# picoAva-Rev3-Boost.net
KiCad netlist of a schematic drawn in EAGLE
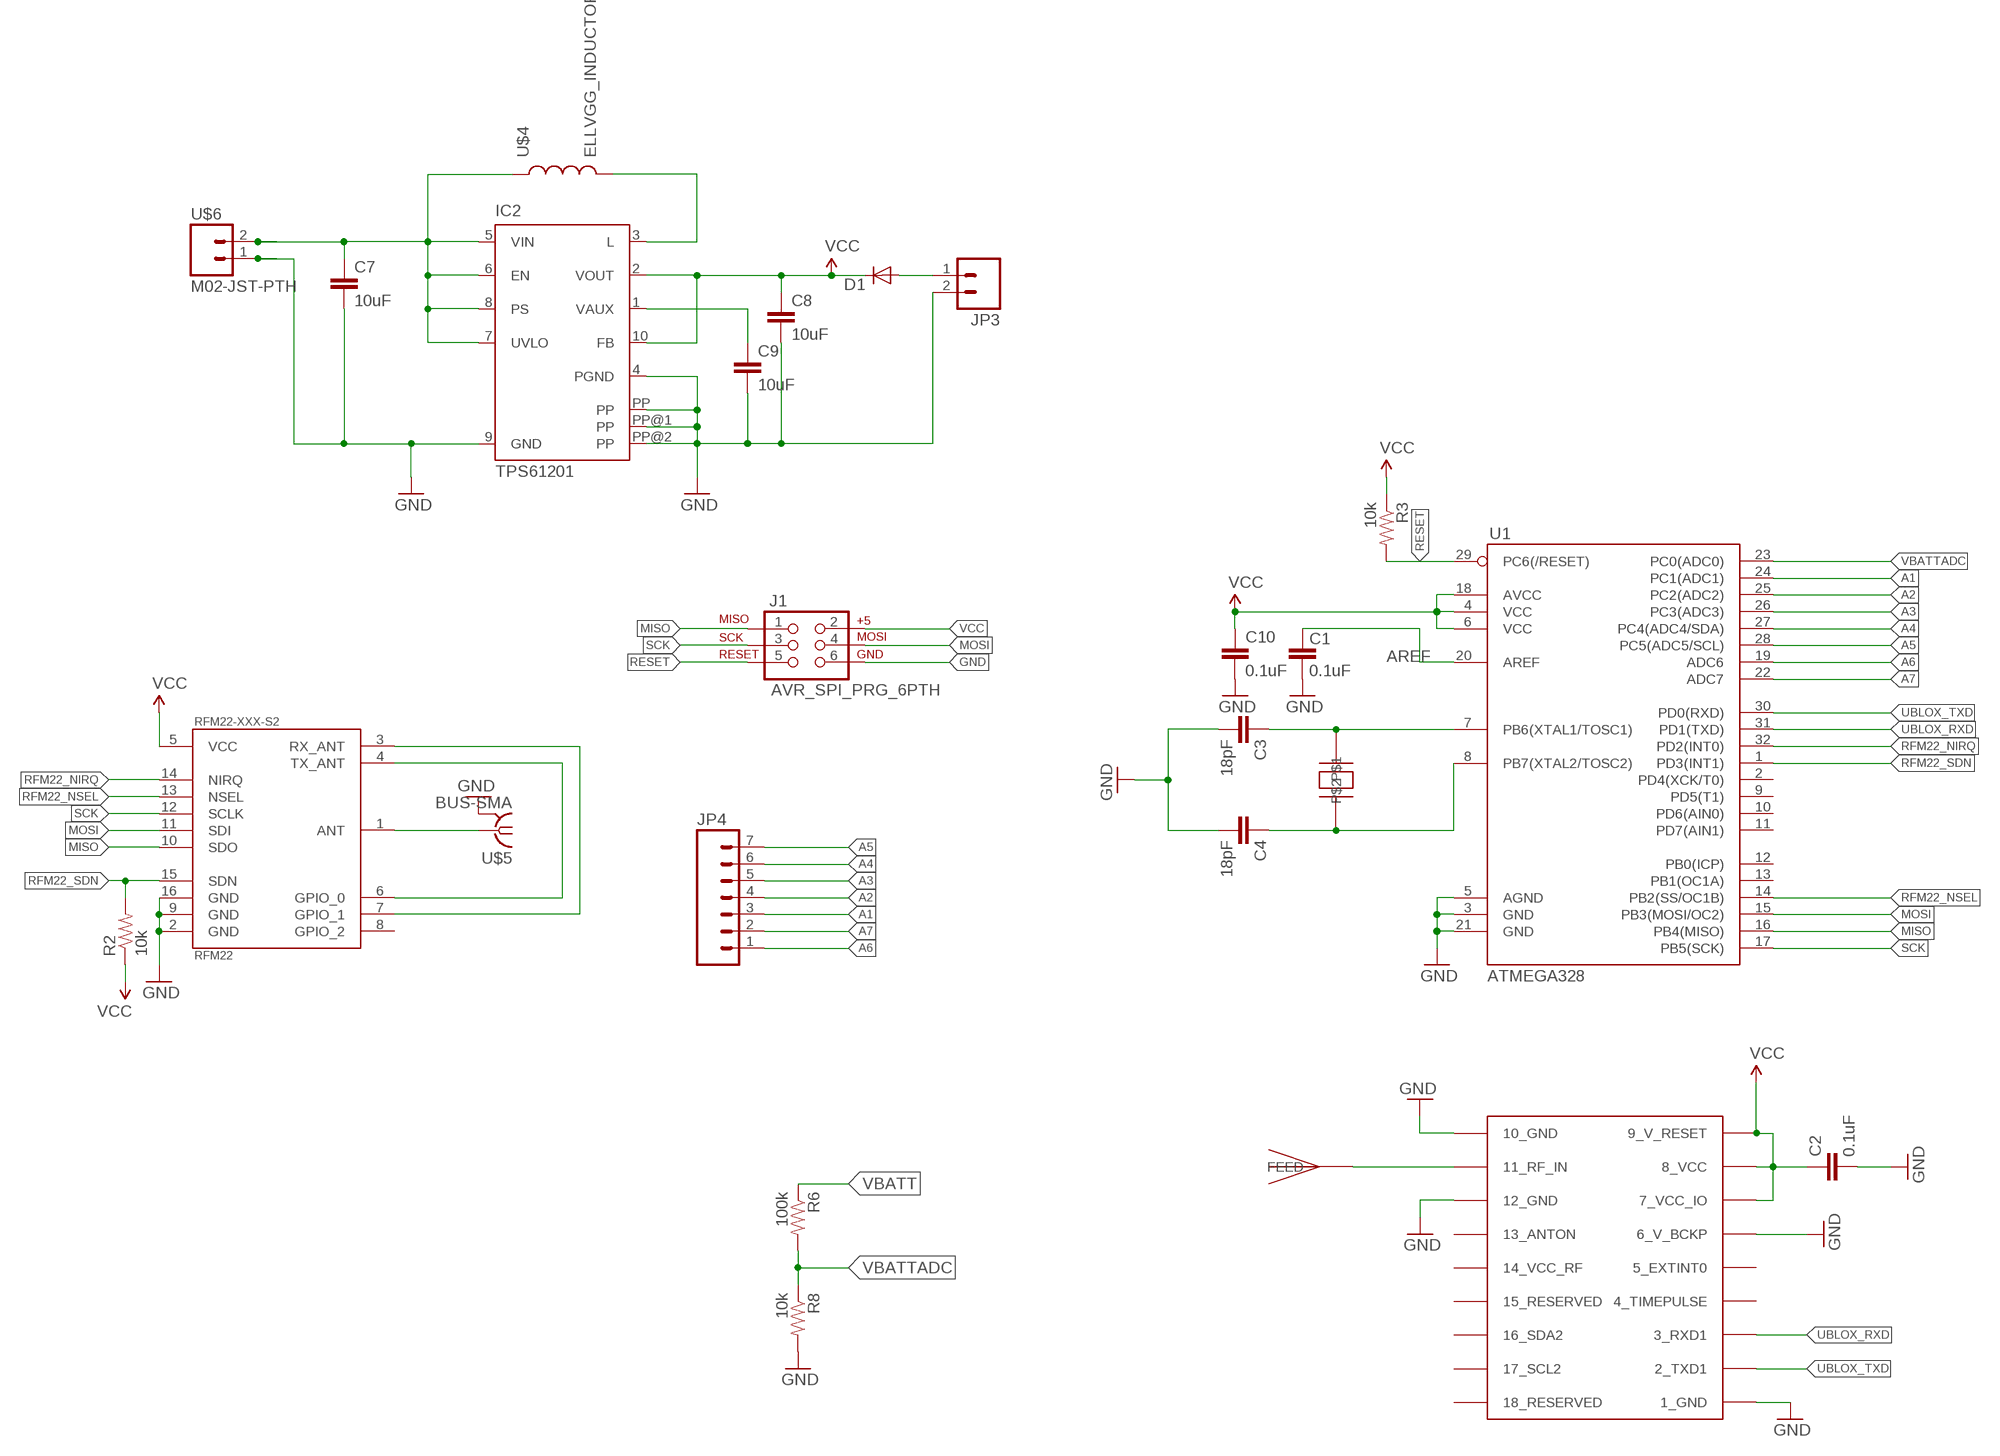
[diagram p0: schematic, sheet 1]

(export (version "E")
  (design (tool "Eeschema 10.0.6"))
  (components
    (comp (ref "C1")
      (value "0.1uF")
      (footprint "eagle-import:0402-CAP")
      (libsource (lib "eagle-import") (part "CAP0402-CAP"))
    )
    (comp (ref "C2")
      (value "0.1uF")
      (footprint "eagle-import:0402-CAP")
      (libsource (lib "eagle-import") (part "CAP0402-CAP"))
    )
    (comp (ref "C3")
      (value "18pF")
      (footprint "eagle-import:0402-CAP")
      (libsource (lib "eagle-import") (part "CAP0402-CAP"))
    )
    (comp (ref "C4")
      (value "18pF")
      (footprint "eagle-import:0402-CAP")
      (libsource (lib "eagle-import") (part "CAP0402-CAP"))
    )
    (comp (ref "C7")
      (value "10uF")
      (footprint "eagle-import:1206")
      (libsource (lib "eagle-import") (part "CAP1206"))
    )
    (comp (ref "C8")
      (value "10uF")
      (footprint "eagle-import:1206")
      (libsource (lib "eagle-import") (part "CAP1206"))
    )
    (comp (ref "C9")
      (value "10uF")
      (footprint "eagle-import:1206")
      (libsource (lib "eagle-import") (part "CAP1206"))
    )
    (comp (ref "C10")
      (value "0.1uF")
      (footprint "eagle-import:0402-CAP")
      (libsource (lib "eagle-import") (part "CAP0402-CAP"))
    )
    (comp (ref "D1")
      (value "DIODESMA")
      (footprint "eagle-import:SMA-DIODE")
      (libsource (lib "eagle-import") (part "DIODESMA"))
    )
    (comp (ref "IC2")
      (value "TPS61201")
      (footprint "eagle-import:S-PDSO-N10")
      (fields (field (name "MPN") "TPS61201DRCT"))
      (libsource (lib "eagle-import") (part "TPS61201"))
    )
    (comp (ref "J1")
      (value "AVR_SPI_PRG_6PTH")
      (footprint "eagle-import:2X3")
      (libsource (lib "eagle-import") (part "AVR_SPI_PRG_6PTH"))
    )
    (comp (ref "JP3")
      (value "M02PTH")
      (footprint "eagle-import:1X02")
      (libsource (lib "eagle-import") (part "M02PTH"))
    )
    (comp (ref "JP4")
      (value "M07")
      (footprint "eagle-import:1X07")
      (libsource (lib "eagle-import") (part "M07"))
    )
    (comp (ref "R2")
      (value "10k")
      (footprint "eagle-import:0402-RES")
      (libsource (lib "eagle-import") (part "RESISTOR0402-RES"))
    )
    (comp (ref "R3")
      (value "10k")
      (footprint "eagle-import:0402-RES")
      (libsource (lib "eagle-import") (part "RESISTOR0402-RES"))
    )
    (comp (ref "R6")
      (value "100k")
      (footprint "eagle-import:0402-RES")
      (libsource (lib "eagle-import") (part "RESISTOR0402-RES"))
    )
    (comp (ref "R8")
      (value "10k")
      (footprint "eagle-import:0402-RES")
      (libsource (lib "eagle-import") (part "RESISTOR0402-RES"))
    )
    (comp (ref "RFM22-XXX-S2")
      (value "RFM22")
      (footprint "eagle-import:RFM22-XXX-S2")
      (libsource (lib "eagle-import") (part "RFM22"))
    )
    (comp (ref "U$1")
      (value "UBLOX_MAX-6")
      (footprint "eagle-import:UBLOX_MAX-6")
      (libsource (lib "eagle-import") (part "UBLOX_MAX-6"))
    )
    (comp (ref "U$2")
      (value "ABRACON_ABM3_CRYSTAL")
      (footprint "eagle-import:ABRACON_ABM3_CRYSTAL")
      (libsource (lib "eagle-import") (part "ABRACON_ABM3_CRYSTAL"))
    )
    (comp (ref "U$3")
      (value "JTI_ANTENNA-1575AT43A40")
      (footprint "eagle-import:JTI_ANTENNA-1575AT43A40")
      (libsource (lib "eagle-import") (part "JTI_ANTENNA-1575AT43A40"))
    )
    (comp (ref "U$4")
      (value "ELLVGG_INDUCTOR")
      (footprint "eagle-import:ELLVGG_INDUCTOR")
      (libsource (lib "eagle-import") (part "ELLVGG_INDUCTOR"))
    )
    (comp (ref "U$5")
      (value "BUS-SMA")
      (footprint "eagle-import:BUS-SMA")
      (libsource (lib "eagle-import") (part "BUS-SMA"))
    )
    (comp (ref "U$6")
      (value "M02-JST-PTH")
      (footprint "eagle-import:M02-JST-PTH")
      (libsource (lib "eagle-import") (part "M02-JST-PTH"))
    )
    (comp (ref "U1")
      (value "ATMEGA328")
      (footprint "eagle-import:TQFP32-08")
      (libsource (lib "eagle-import") (part "ATMEGA168"))
    )
  )
  (nets
    (net (code "1") (name "/AREF") (class "Default")
      (node (ref "C1") (pin "2") (pinfunction "2_2") (pintype "passive"))
      (node (ref "U1") (pin "20") (pinfunction "AREF_20") (pintype "bidirectional"))
    )
    (net (code "2") (name "A1") (class "Default")
      (node (ref "JP4") (pin "3") (pinfunction "3_3") (pintype "passive"))
      (node (ref "U1") (pin "24") (pinfunction "PC1(ADC1)_24") (pintype "bidirectional"))
    )
    (net (code "3") (name "A2") (class "Default")
      (node (ref "JP4") (pin "4") (pinfunction "4_4") (pintype "passive"))
      (node (ref "U1") (pin "25") (pinfunction "PC2(ADC2)_25") (pintype "bidirectional"))
    )
    (net (code "4") (name "A3") (class "Default")
      (node (ref "JP4") (pin "5") (pinfunction "5_5") (pintype "passive"))
      (node (ref "U1") (pin "26") (pinfunction "PC3(ADC3)_26") (pintype "bidirectional"))
    )
    (net (code "5") (name "A4") (class "Default")
      (node (ref "JP4") (pin "6") (pinfunction "6_6") (pintype "passive"))
      (node (ref "U1") (pin "27") (pinfunction "PC4(ADC4/SDA)_27") (pintype "bidirectional"))
    )
    (net (code "6") (name "A5") (class "Default")
      (node (ref "JP4") (pin "7") (pinfunction "7_7") (pintype "passive"))
      (node (ref "U1") (pin "28") (pinfunction "PC5(ADC5/SCL)_28") (pintype "bidirectional"))
    )
    (net (code "7") (name "A6") (class "Default")
      (node (ref "JP4") (pin "1") (pinfunction "1_1") (pintype "passive"))
      (node (ref "U1") (pin "19") (pinfunction "ADC6_19") (pintype "bidirectional"))
    )
    (net (code "8") (name "A7") (class "Default")
      (node (ref "JP4") (pin "2") (pinfunction "2_2") (pintype "passive"))
      (node (ref "U1") (pin "22") (pinfunction "ADC7_22") (pintype "bidirectional"))
    )
    (net (code "9") (name "GND") (class "Default")
      (node (ref "C1") (pin "1") (pinfunction "1_1") (pintype "passive"))
      (node (ref "C10") (pin "2") (pinfunction "2_2") (pintype "passive"))
      (node (ref "C2") (pin "2") (pinfunction "2_2") (pintype "passive"))
      (node (ref "C3") (pin "2") (pinfunction "2_2") (pintype "passive"))
      (node (ref "C4") (pin "2") (pinfunction "2_2") (pintype "passive"))
      (node (ref "C7") (pin "2") (pinfunction "2_2") (pintype "passive"))
      (node (ref "C8") (pin "2") (pinfunction "2_2") (pintype "passive"))
      (node (ref "C9") (pin "2") (pinfunction "2_2") (pintype "passive"))
      (node (ref "IC2") (pin "4") (pinfunction "PGND_4") (pintype "power_in"))
      (node (ref "IC2") (pin "9") (pinfunction "GND_9") (pintype "power_in"))
      (node (ref "IC2") (pin "PP") (pinfunction "PP_PP") (pintype "power_in"))
      (node (ref "IC2") (pin "PP@1") (pinfunction "PP_PP@1") (pintype "power_in"))
      (node (ref "IC2") (pin "PP@2") (pinfunction "PP_PP@2") (pintype "power_in"))
      (node (ref "J1") (pin "6") (pinfunction "6_6") (pintype "passive"))
      (node (ref "JP3") (pin "2") (pinfunction "2_2") (pintype "passive"))
      (node (ref "R8") (pin "2") (pinfunction "2_2") (pintype "passive"))
      (node (ref "RFM22-XXX-S2") (pin "16") (pinfunction "GND_16") (pintype "power_in"))
      (node (ref "RFM22-XXX-S2") (pin "2") (pinfunction "GND_2") (pintype "power_in"))
      (node (ref "RFM22-XXX-S2") (pin "9") (pinfunction "GND_9") (pintype "power_in"))
      (node (ref "U$1") (pin "10_GND") (pinfunction "10_GND_10_GND") (pintype "bidirectional"))
      (node (ref "U$1") (pin "12_GND") (pinfunction "12_GND_12_GND") (pintype "bidirectional"))
      (node (ref "U$1") (pin "1_GND") (pinfunction "1_GND_1_GND") (pintype "bidirectional"))
      (node (ref "U$1") (pin "6_V_BCKP") (pinfunction "6_V_BCKP_6_V_BCKP") (pintype "bidirectional"))
      (node (ref "U$5") (pin "2") (pinfunction "GND_2") (pintype "power_in"))
      (node (ref "U$5") (pin "3") (pinfunction "GND_3") (pintype "power_in"))
      (node (ref "U$5") (pin "4") (pinfunction "GND_4") (pintype "power_in"))
      (node (ref "U$5") (pin "5") (pinfunction "GND_5") (pintype "power_in"))
      (node (ref "U$6") (pin "1") (pinfunction "1_1") (pintype "passive"))
      (node (ref "U1") (pin "21") (pinfunction "GND_21") (pintype "bidirectional"))
      (node (ref "U1") (pin "3") (pinfunction "GND_3") (pintype "bidirectional"))
      (node (ref "U1") (pin "5") (pinfunction "AGND_5") (pintype "bidirectional"))
    )
    (net (code "10") (name "MISO") (class "Default")
      (node (ref "J1") (pin "1") (pinfunction "1_1") (pintype "passive"))
      (node (ref "RFM22-XXX-S2") (pin "10") (pinfunction "SDO_10") (pintype "output"))
      (node (ref "U1") (pin "16") (pinfunction "PB4(MISO)_16") (pintype "bidirectional"))
    )
    (net (code "11") (name "MOSI") (class "Default")
      (node (ref "J1") (pin "4") (pinfunction "4_4") (pintype "passive"))
      (node (ref "RFM22-XXX-S2") (pin "11") (pinfunction "SDI_11") (pintype "input"))
      (node (ref "U1") (pin "15") (pinfunction "PB3(MOSI/OC2)_15") (pintype "bidirectional"))
    )
    (net (code "12") (name "Net-(D1-PadA)") (class "Default")
      (node (ref "D1") (pin "A") (pinfunction "A_A") (pintype "passive"))
      (node (ref "JP3") (pin "1") (pinfunction "1_1") (pintype "passive"))
    )
    (net (code "13") (name "Net-(IC2-L)") (class "Default")
      (node (ref "IC2") (pin "3") (pinfunction "L_3") (pintype "input"))
      (node (ref "U$4") (pin "P$2") (pinfunction "2_P$2") (pintype "passive"))
    )
    (net (code "14") (name "Net-(IC2-VAUX)") (class "Default")
      (node (ref "C9") (pin "1") (pinfunction "1_1") (pintype "passive"))
      (node (ref "IC2") (pin "1") (pinfunction "VAUX_1") (pintype "bidirectional"))
    )
    (net (code "15") (name "Net-(RFM22-XXX-S2-ANT)") (class "Default")
      (node (ref "RFM22-XXX-S2") (pin "1") (pinfunction "ANT_1") (pintype "bidirectional"))
      (node (ref "U$5") (pin "1") (pinfunction "1_1") (pintype "passive"))
    )
    (net (code "16") (name "Net-(RFM22-XXX-S2-GPIO_0)") (class "Default")
      (node (ref "RFM22-XXX-S2") (pin "4") (pinfunction "TX_ANT_4") (pintype "input"))
      (node (ref "RFM22-XXX-S2") (pin "6") (pinfunction "GPIO_0_6") (pintype "bidirectional"))
    )
    (net (code "17") (name "Net-(RFM22-XXX-S2-GPIO_1)") (class "Default")
      (node (ref "RFM22-XXX-S2") (pin "3") (pinfunction "RX_ANT_3") (pintype "input"))
      (node (ref "RFM22-XXX-S2") (pin "7") (pinfunction "GPIO_1_7") (pintype "bidirectional"))
    )
    (net (code "18") (name "Net-(U$1-Pad11_RF_IN)") (class "Default")
      (node (ref "U$1") (pin "11_RF_IN") (pinfunction "11_RF_IN_11_RF_IN") (pintype "bidirectional"))
      (node (ref "U$3") (pin "FEED") (pinfunction "FEED_FEED") (pintype "bidirectional"))
    )
    (net (code "19") (name "Net-(U1-PB6(XTAL1{slash}TOSC1))") (class "Default")
      (node (ref "C3") (pin "1") (pinfunction "1_1") (pintype "passive"))
      (node (ref "U$2") (pin "P$2") (pinfunction "P$2_P$2") (pintype "bidirectional"))
      (node (ref "U1") (pin "7") (pinfunction "PB6(XTAL1/TOSC1)_7") (pintype "bidirectional"))
    )
    (net (code "20") (name "Net-(U1-PB7(XTAL2{slash}TOSC2))") (class "Default")
      (node (ref "C4") (pin "1") (pinfunction "1_1") (pintype "passive"))
      (node (ref "U$2") (pin "P$1") (pinfunction "P$1_P$1") (pintype "bidirectional"))
      (node (ref "U1") (pin "8") (pinfunction "PB7(XTAL2/TOSC2)_8") (pintype "bidirectional"))
    )
    (net (code "21") (name "RESET") (class "Default")
      (node (ref "J1") (pin "5") (pinfunction "5_5") (pintype "passive"))
      (node (ref "R3") (pin "2") (pinfunction "2_2") (pintype "passive"))
      (node (ref "U1") (pin "29") (pinfunction "PC6(/RESET)_29") (pintype "bidirectional"))
    )
    (net (code "22") (name "RFM22_NIRQ") (class "Default")
      (node (ref "RFM22-XXX-S2") (pin "14") (pinfunction "NIRQ_14") (pintype "output"))
      (node (ref "U1") (pin "32") (pinfunction "PD2(INT0)_32") (pintype "bidirectional"))
    )
    (net (code "23") (name "RFM22_NSEL") (class "Default")
      (node (ref "RFM22-XXX-S2") (pin "13") (pinfunction "NSEL_13") (pintype "input"))
      (node (ref "U1") (pin "14") (pinfunction "PB2(SS/OC1B)_14") (pintype "bidirectional"))
    )
    (net (code "24") (name "RFM22_SDN") (class "Default")
      (node (ref "R2") (pin "2") (pinfunction "2_2") (pintype "passive"))
      (node (ref "RFM22-XXX-S2") (pin "15") (pinfunction "SDN_15") (pintype "input"))
      (node (ref "U1") (pin "1") (pinfunction "PD3(INT1)_1") (pintype "bidirectional"))
    )
    (net (code "25") (name "SCK") (class "Default")
      (node (ref "J1") (pin "3") (pinfunction "3_3") (pintype "passive"))
      (node (ref "RFM22-XXX-S2") (pin "12") (pinfunction "SCLK_12") (pintype "input"))
      (node (ref "U1") (pin "17") (pinfunction "PB5(SCK)_17") (pintype "bidirectional"))
    )
    (net (code "26") (name "UBLOX_RXD") (class "Default")
      (node (ref "U$1") (pin "3_RXD1") (pinfunction "3_RXD1_3_RXD1") (pintype "bidirectional"))
      (node (ref "U1") (pin "31") (pinfunction "PD1(TXD)_31") (pintype "bidirectional"))
    )
    (net (code "27") (name "UBLOX_TXD") (class "Default")
      (node (ref "U$1") (pin "2_TXD1") (pinfunction "2_TXD1_2_TXD1") (pintype "bidirectional"))
      (node (ref "U1") (pin "30") (pinfunction "PD0(RXD)_30") (pintype "bidirectional"))
    )
    (net (code "28") (name "VBATT") (class "Default")
      (node (ref "C7") (pin "1") (pinfunction "1_1") (pintype "passive"))
      (node (ref "IC2") (pin "5") (pinfunction "VIN_5") (pintype "input"))
      (node (ref "IC2") (pin "6") (pinfunction "EN_6") (pintype "input"))
      (node (ref "IC2") (pin "7") (pinfunction "UVLO_7") (pintype "input"))
      (node (ref "IC2") (pin "8") (pinfunction "PS_8") (pintype "input"))
      (node (ref "R6") (pin "1") (pinfunction "1_1") (pintype "passive"))
      (node (ref "U$4") (pin "P$1") (pinfunction "1_P$1") (pintype "passive"))
      (node (ref "U$6") (pin "2") (pinfunction "2_2") (pintype "passive"))
    )
    (net (code "29") (name "VBATTADC") (class "Default")
      (node (ref "R6") (pin "2") (pinfunction "2_2") (pintype "passive"))
      (node (ref "R8") (pin "1") (pinfunction "1_1") (pintype "passive"))
      (node (ref "U1") (pin "23") (pinfunction "PC0(ADC0)_23") (pintype "bidirectional"))
    )
    (net (code "30") (name "VCC") (class "Default")
      (node (ref "C10") (pin "1") (pinfunction "1_1") (pintype "passive"))
      (node (ref "C2") (pin "1") (pinfunction "1_1") (pintype "passive"))
      (node (ref "C8") (pin "1") (pinfunction "1_1") (pintype "passive"))
      (node (ref "D1") (pin "C") (pinfunction "C_C") (pintype "passive"))
      (node (ref "IC2") (pin "10") (pinfunction "FB_10") (pintype "input"))
      (node (ref "IC2") (pin "2") (pinfunction "VOUT_2") (pintype "passive"))
      (node (ref "J1") (pin "2") (pinfunction "2_2") (pintype "passive"))
      (node (ref "R2") (pin "1") (pinfunction "1_1") (pintype "passive"))
      (node (ref "R3") (pin "1") (pinfunction "1_1") (pintype "passive"))
      (node (ref "RFM22-XXX-S2") (pin "5") (pinfunction "VCC_5") (pintype "bidirectional"))
      (node (ref "U$1") (pin "7_VCC_IO") (pinfunction "7_VCC_IO_7_VCC_IO") (pintype "bidirectional"))
      (node (ref "U$1") (pin "8_VCC") (pinfunction "8_VCC_8_VCC") (pintype "bidirectional"))
      (node (ref "U$1") (pin "9_V_RESET") (pinfunction "9_V_RESET_9_V_RESET") (pintype "bidirectional"))
      (node (ref "U1") (pin "18") (pinfunction "AVCC_18") (pintype "bidirectional"))
      (node (ref "U1") (pin "4") (pinfunction "VCC_4") (pintype "bidirectional"))
      (node (ref "U1") (pin "6") (pinfunction "VCC_6") (pintype "bidirectional"))
    )
    (net (code "31") (name "unconnected-(RFM22-XXX-S2-GPIO_2-Pad8)") (class "Default")
      (node (ref "RFM22-XXX-S2") (pin "8") (pinfunction "GPIO_2_8") (pintype "bidirectional"))
    )
    (net (code "32") (name "unconnected-(U$1-Pad4_TIMEPULSE)") (class "Default")
      (node (ref "U$1") (pin "4_TIMEPULSE") (pinfunction "4_TIMEPULSE_4_TIMEPULSE") (pintype "bidirectional"))
    )
    (net (code "33") (name "unconnected-(U$1-Pad5_EXTINT0)") (class "Default")
      (node (ref "U$1") (pin "5_EXTINT0") (pinfunction "5_EXTINT0_5_EXTINT0") (pintype "bidirectional"))
    )
    (net (code "34") (name "unconnected-(U$1-Pad13_ANTON)") (class "Default")
      (node (ref "U$1") (pin "13_ANTON") (pinfunction "13_ANTON_13_ANTON") (pintype "bidirectional"))
    )
    (net (code "35") (name "unconnected-(U$1-Pad14_VCC_RF)") (class "Default")
      (node (ref "U$1") (pin "14_VCC_RF") (pinfunction "14_VCC_RF_14_VCC_RF") (pintype "bidirectional"))
    )
    (net (code "36") (name "unconnected-(U$1-Pad15_RESERVED)") (class "Default")
      (node (ref "U$1") (pin "15_RESERVED") (pinfunction "15_RESERVED_15_RESERVED") (pintype "bidirectional"))
    )
    (net (code "37") (name "unconnected-(U$1-Pad16_SDA2)") (class "Default")
      (node (ref "U$1") (pin "16_SDA2") (pinfunction "16_SDA2_16_SDA2") (pintype "bidirectional"))
    )
    (net (code "38") (name "unconnected-(U$1-Pad17_SCL2)") (class "Default")
      (node (ref "U$1") (pin "17_SCL2") (pinfunction "17_SCL2_17_SCL2") (pintype "bidirectional"))
    )
    (net (code "39") (name "unconnected-(U$1-Pad18_RESERVED)") (class "Default")
      (node (ref "U$1") (pin "18_RESERVED") (pinfunction "18_RESERVED_18_RESERVED") (pintype "bidirectional"))
    )
    (net (code "40") (name "unconnected-(U1-PB0(ICP)-Pad12)") (class "Default")
      (node (ref "U1") (pin "12") (pinfunction "PB0(ICP)_12") (pintype "bidirectional"))
    )
    (net (code "41") (name "unconnected-(U1-PB1(OC1A)-Pad13)") (class "Default")
      (node (ref "U1") (pin "13") (pinfunction "PB1(OC1A)_13") (pintype "bidirectional"))
    )
    (net (code "42") (name "unconnected-(U1-PD4(XCK{slash}T0)-Pad2)") (class "Default")
      (node (ref "U1") (pin "2") (pinfunction "PD4(XCK/T0)_2") (pintype "bidirectional"))
    )
    (net (code "43") (name "unconnected-(U1-PD5(T1)-Pad9)") (class "Default")
      (node (ref "U1") (pin "9") (pinfunction "PD5(T1)_9") (pintype "bidirectional"))
    )
    (net (code "44") (name "unconnected-(U1-PD6(AIN0)-Pad10)") (class "Default")
      (node (ref "U1") (pin "10") (pinfunction "PD6(AIN0)_10") (pintype "bidirectional"))
    )
    (net (code "45") (name "unconnected-(U1-PD7(AIN1)-Pad11)") (class "Default")
      (node (ref "U1") (pin "11") (pinfunction "PD7(AIN1)_11") (pintype "bidirectional"))
    )
  )
)
